# P05_BOOT_SET_KEY_LED_SPI_ADC.net
KiCad netlist of a schematic drawn in Altium Designer
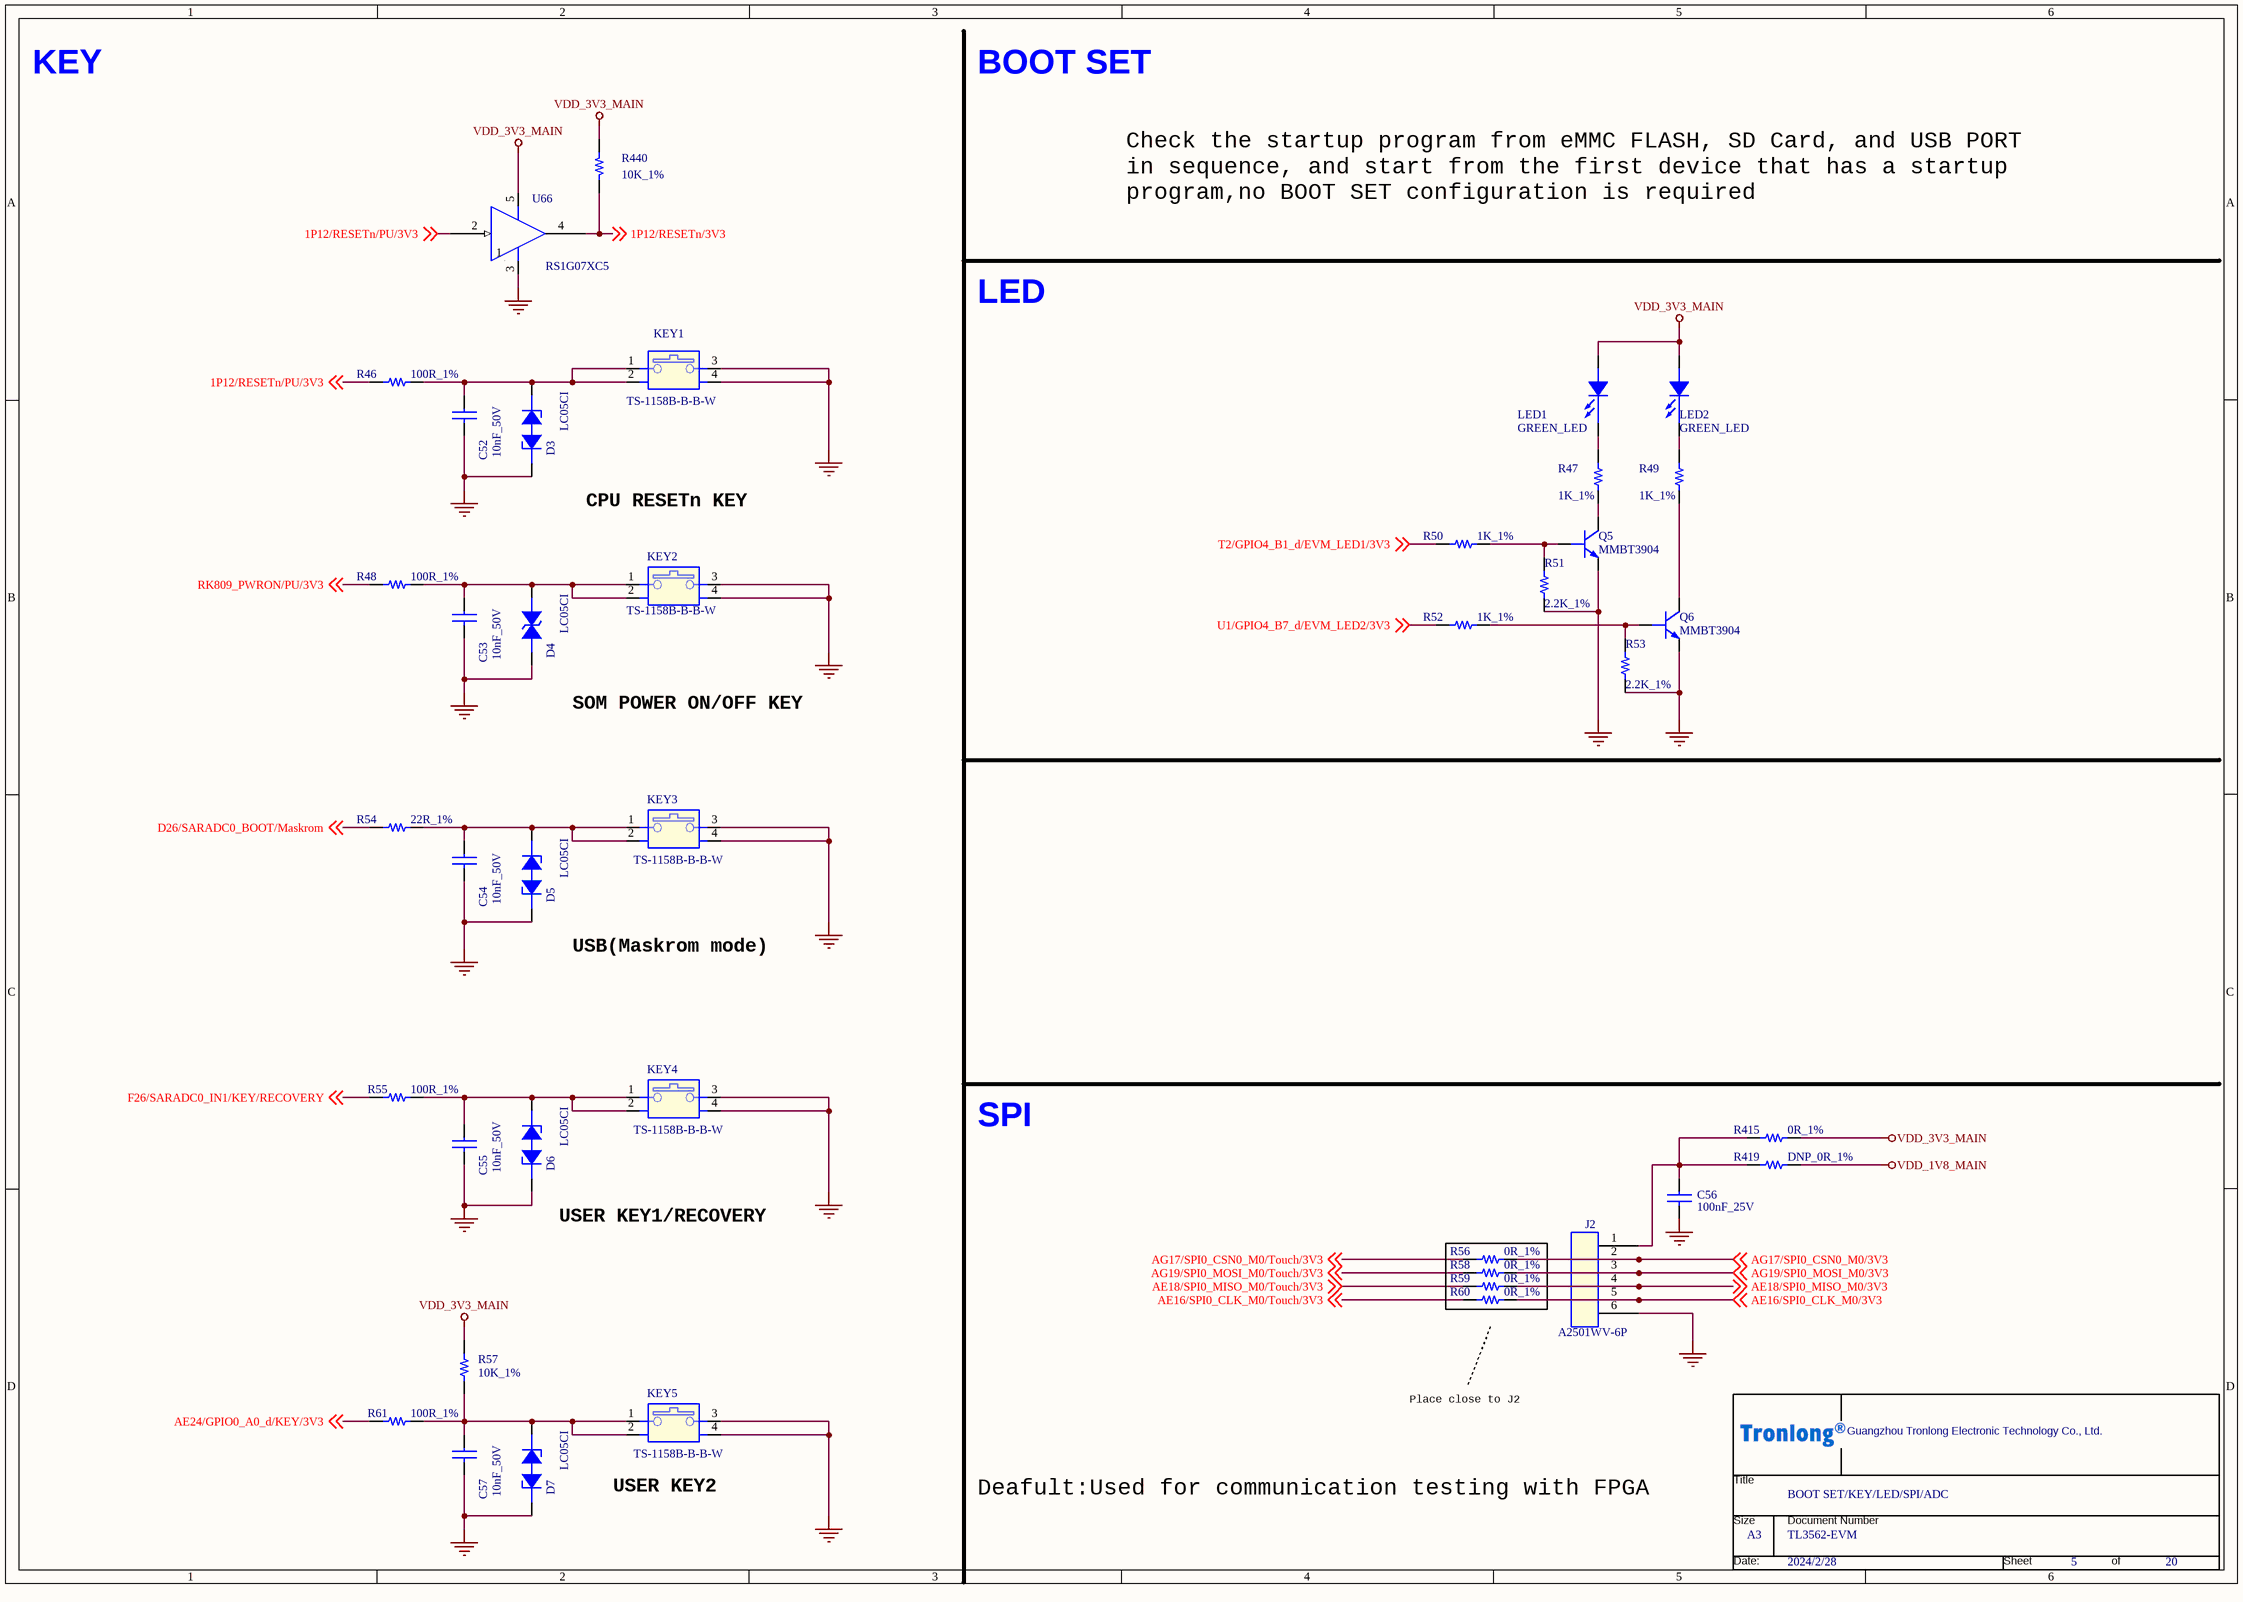
[diagram p0: P05_BOOT SET_KEY_LED_SPI_ADC.SchDoc]

(export (version "E")
  (design (tool "Eeschema 10.0.6"))
  (components
    (comp (ref "C52")
      (value "10nF_50V")
      (footprint "C0402")
      (description "贴片陶瓷电容,10nF,10%,50V,X7R")
      (libsource (lib "*") (part "CAP NP_Dup2"))
    )
    (comp (ref "C53")
      (value "10nF_50V")
      (footprint "C0402")
      (description "贴片陶瓷电容,10nF,10%,50V,X7R")
      (libsource (lib "*") (part "CAP NP_Dup2"))
    )
    (comp (ref "C54")
      (value "10nF_50V")
      (footprint "C0402")
      (description "贴片陶瓷电容,10nF,10%,50V,X7R")
      (libsource (lib "*") (part "CAP NP_Dup2"))
    )
    (comp (ref "C55")
      (value "10nF_50V")
      (footprint "C0402")
      (description "贴片陶瓷电容,10nF,10%,50V,X7R")
      (libsource (lib "*") (part "CAP NP_Dup2"))
    )
    (comp (ref "C56")
      (value "100nF_25V")
      (footprint "C0402")
      (description "贴片陶瓷电容,100nF,10%,25V,X5R")
      (libsource (lib "*") (part "CAP NP_Dup3"))
    )
    (comp (ref "C57")
      (value "10nF_50V")
      (footprint "C0402")
      (description "贴片陶瓷电容,10nF,10%,50V,X7R")
      (libsource (lib "*") (part "CAP NP_Dup2"))
    )
    (comp (ref "D3")
      (value "LC05CI")
      (footprint "SOD323_BI")
      (description "TVS二极管,VRWM=5V,VBR=6V,一组,双向,30KV,30KV")
      (fields
        (field (name "MANUFACTURER PART NUMBER") "PESD3V3L1BA")
        (field (name "MANUFACTURER") "上海雷卯电子科技有限公司（Leiditech）")
      )
      (libsource (lib "*") (part "DIODE BREAKDOWN_2"))
    )
    (comp (ref "D4")
      (value "LC05CI")
      (footprint "SOD323_BI")
      (description "TVS二极管,VRWM=5V,VBR=6V,一组,双向,30KV,30KV")
      (fields
        (field (name "MANUFACTURER PART NUMBER") "PESD3V3L1BA")
        (field (name "MANUFACTURER") "上海雷卯电子科技有限公司（Leiditech）")
      )
      (libsource (lib "*") (part "DIODE-BI"))
    )
    (comp (ref "D5")
      (value "LC05CI")
      (footprint "SOD323_BI")
      (description "TVS二极管,VRWM=5V,VBR=6V,一组,双向,30KV,30KV")
      (fields
        (field (name "MANUFACTURER") "上海雷卯电子科技有限公司（Leiditech）")
        (field (name "MANUFACTURER PART NUMBER") "PESD3V3L1BA")
      )
      (libsource (lib "*") (part "DIODE BREAKDOWN_2"))
    )
    (comp (ref "D6")
      (value "LC05CI")
      (footprint "SOD323_BI")
      (description "TVS二极管,VRWM=5V,VBR=6V,一组,双向,30KV,30KV")
      (fields
        (field (name "MANUFACTURER PART NUMBER") "PESD3V3L1BA")
        (field (name "MANUFACTURER") "上海雷卯电子科技有限公司（Leiditech）")
      )
      (libsource (lib "*") (part "DIODE BREAKDOWN_2"))
    )
    (comp (ref "D7")
      (value "LC05CI")
      (footprint "SOD323_BI")
      (description "TVS二极管,VRWM=5V,VBR=6V,一组,双向,30KV,30KV")
      (fields
        (field (name "MANUFACTURER") "上海雷卯电子科技有限公司（Leiditech）")
        (field (name "MANUFACTURER PART NUMBER") "PESD3V3L1BA")
      )
      (libsource (lib "*") (part "DIODE BREAKDOWN_2"))
    )
    (comp (ref "J2")
      (value "A2501WV-6P")
      (footprint "CON_XH_1x6P_2D54_H_M_DIP")
      (description "XH2.54  6P 连接器 180度")
      (fields (field (name "MANUFACTURER") "深圳市长江连接器有限公司（CJT）"))
      (libsource (lib "*") (part "CON6_Dup1"))
    )
    (comp (ref "KEY1")
      (value "TS-1158B-B-B-W")
      (footprint "TS-1158B-B-B-W")
      (description "四脚方形按键6.4x6.5，2.5mm+1.8mm，白色硅胶键帽")
      (fields (field (name "MANUFACTURER") "广东星坤科技股份有限公司（XKB）"))
      (libsource (lib "*") (part "SW PUSHBUTTON-SPST SHIELD_0"))
    )
    (comp (ref "KEY2")
      (value "TS-1158B-B-B-W")
      (footprint "TS-1158B-B-B-W")
      (description "四脚方形按键6.4x6.5，2.5mm+1.8mm，白色硅胶键帽")
      (fields (field (name "MANUFACTURER") "广东星坤科技股份有限公司（XKB）"))
      (libsource (lib "*") (part "SW PUSHBUTTON-SPST SHIELD_0"))
    )
    (comp (ref "KEY3")
      (value "TS-1158B-B-B-W")
      (footprint "TS-1158B-B-B-W")
      (description "四脚方形按键6.4x6.5，2.5mm+1.8mm，白色硅胶键帽")
      (fields (field (name "MANUFACTURER") "广东星坤科技股份有限公司（XKB）"))
      (libsource (lib "*") (part "SW PUSHBUTTON-SPST SHIELD_0"))
    )
    (comp (ref "KEY4")
      (value "TS-1158B-B-B-W")
      (footprint "TS-1158B-B-B-W")
      (description "四脚方形按键6.4x6.5，2.5mm+1.8mm，白色硅胶键帽")
      (fields (field (name "MANUFACTURER") "广东星坤科技股份有限公司（XKB）"))
      (libsource (lib "*") (part "SW PUSHBUTTON-SPST SHIELD_0"))
    )
    (comp (ref "KEY5")
      (value "TS-1158B-B-B-W")
      (footprint "TS-1158B-B-B-W")
      (description "四脚方形按键6.4x6.5，2.5mm+1.8mm，白色硅胶键帽")
      (fields (field (name "MANUFACTURER") "广东星坤科技股份有限公司（XKB）"))
      (libsource (lib "*") (part "SW PUSHBUTTON-SPST SHIELD_0"))
    )
    (comp (ref "LED1")
      (value "GREEN_LED")
      (footprint "CON_2P_3MM")
      (description "直插式发光二极管,绿色,带灯座")
      (fields
        (field (name "MANUFACTURER") "深圳市巨弘光电有限公司（JUHLIGHT）")
        (field (name "MANUFACTURER PARTNUMBER") "JH-03B2YG1E-DL")
      )
      (libsource (lib "*") (part "LED_0"))
    )
    (comp (ref "LED2")
      (value "GREEN_LED")
      (footprint "CON_2P_3MM")
      (description "直插式发光二极管,绿色,带灯座")
      (fields
        (field (name "MANUFACTURER PARTNUMBER") "JH-03B2YG1E-DL")
        (field (name "MANUFACTURER") "深圳市巨弘光电有限公司（JUHLIGHT）")
      )
      (libsource (lib "*") (part "LED_0"))
    )
    (comp (ref "Q5")
      (value "MMBT3904")
      (footprint "SOT23-3_DBZ3")
      (description "BJT,NPN,Vceo=40V,Ic=200mA,fT=300MHz,PD=200mW")
      (fields (field (name "MANUFACTURER") "江苏长晶科技有限公司（JSCJ）"))
      (libsource (lib "*") (part "MMBT3904/SOT"))
    )
    (comp (ref "Q6")
      (value "MMBT3904")
      (footprint "SOT23-3_DBZ3")
      (description "BJT,NPN,Vceo=40V,Ic=200mA,fT=300MHz,PD=200mW")
      (fields (field (name "MANUFACTURER") "江苏长晶科技有限公司（JSCJ）"))
      (libsource (lib "*") (part "MMBT3904/SOT"))
    )
    (comp (ref "R46")
      (value "100R_1%")
      (footprint "R0603")
      (description "贴片电阻,100R,±1%,1/10W")
      (libsource (lib "*") (part "Resistor_Dup2"))
    )
    (comp (ref "R47")
      (value "1K_1%")
      (footprint "R0402")
      (description "贴片电阻,1K,±1%,1/16W")
      (libsource (lib "*") (part "Resistor_Dup3"))
    )
    (comp (ref "R48")
      (value "100R_1%")
      (footprint "R0603")
      (description "贴片电阻,100R,±1%,1/10W")
      (libsource (lib "*") (part "Resistor_Dup2"))
    )
    (comp (ref "R49")
      (value "1K_1%")
      (footprint "R0402")
      (description "贴片电阻,1K,±1%,1/16W")
      (libsource (lib "*") (part "Resistor_Dup3"))
    )
    (comp (ref "R50")
      (value "1K_1%")
      (footprint "R0402")
      (description "贴片电阻,1K,±1%,1/16W")
      (libsource (lib "*") (part "Resistor_Dup3"))
    )
    (comp (ref "R51")
      (value "2.2K_1%")
      (footprint "R0603")
      (description "贴片电阻,2.2K,±1%,1/10W")
      (libsource (lib "*") (part "Resistor_Dup3"))
    )
    (comp (ref "R52")
      (value "1K_1%")
      (footprint "R0402")
      (description "贴片电阻,1K,±1%,1/16W")
      (libsource (lib "*") (part "Resistor_Dup3"))
    )
    (comp (ref "R53")
      (value "2.2K_1%")
      (footprint "R0603")
      (description "贴片电阻,2.2K,±1%,1/10W")
      (libsource (lib "*") (part "Resistor_Dup3"))
    )
    (comp (ref "R54")
      (value "22R_1%")
      (footprint "R0402")
      (description "贴片电阻,22R,±1%,1/16W")
      (libsource (lib "*") (part "Resistor_Dup2"))
    )
    (comp (ref "R55")
      (value "100R_1%")
      (footprint "R0603")
      (description "贴片电阻,100R,±1%,1/10W")
      (libsource (lib "*") (part "Resistor_Dup2"))
    )
    (comp (ref "R56")
      (value "0R_1%")
      (footprint "R0402")
      (description "0R,±1%,R0402,≥1/16W")
      (libsource (lib "*") (part "Resistor_Dup3"))
    )
    (comp (ref "R57")
      (value "10K_1%")
      (footprint "R0402")
      (description "贴片电阻,10K,±1%,1/16W")
      (libsource (lib "*") (part "Resistor_Dup2"))
    )
    (comp (ref "R58")
      (value "0R_1%")
      (footprint "R0402")
      (description "0R,±1%,R0402,≥1/16W")
      (libsource (lib "*") (part "Resistor_Dup3"))
    )
    (comp (ref "R59")
      (value "0R_1%")
      (footprint "R0402")
      (description "0R,±1%,R0402,≥1/16W")
      (libsource (lib "*") (part "Resistor_Dup3"))
    )
    (comp (ref "R60")
      (value "0R_1%")
      (footprint "R0402")
      (description "0R,±1%,R0402,≥1/16W")
      (libsource (lib "*") (part "Resistor_Dup3"))
    )
    (comp (ref "R61")
      (value "100R_1%")
      (footprint "R0603")
      (description "贴片电阻,100R,±1%,1/10W")
      (libsource (lib "*") (part "Resistor_Dup2"))
    )
    (comp (ref "R415")
      (value "0R_1%")
      (footprint "R0603")
      (description "0R,±1%,R0603,≥1/10W")
      (libsource (lib "*") (part "Resistor_Dup3"))
    )
    (comp (ref "R419")
      (value "DNP_0R_1%")
      (footprint "R0603")
      (description "贴片电阻,0R,±1%,1/10W")
      (libsource (lib "*") (part "Resistor_Dup3"))
    )
    (comp (ref "R440")
      (value "10K_1%")
      (footprint "R0402")
      (description "贴片电阻,10K,±1%,1/16W")
      (libsource (lib "*") (part "Resistor"))
    )
    (comp (ref "U66")
      (value "RS1G07XC5")
      (footprint "SC70-5-43M")
      (description "1个1位缓冲器")
      (fields (field (name "MFR") "TI") (field (name "TIINTPARTNUMBER") "1A0269"))
      (libsource (lib "*") (part "1A_SN74LVC1G07"))
    )
  )
  (nets
    (net (code "1") (name "1P12{slash}RESETn{slash}3V3") (class "Default")
      (node (ref "R440") (pin "1") (pinfunction "1_1") (pintype "passive"))
      (node (ref "U66") (pin "4") (pinfunction "Y_4") (pintype "open_collector"))
    )
    (net (code "2") (name "1P12{slash}RESETn{slash}PU{slash}3V3") (class "Default")
      (node (ref "R46") (pin "1") (pinfunction "1_1") (pintype "passive"))
      (node (ref "U66") (pin "2") (pinfunction "A_2") (pintype "input"))
    )
    (net (code "3") (name "AE16{slash}SPI0_CLK_M0{slash}3V3") (class "Default")
      (node (ref "J2") (pin "5") (pinfunction "5_5") (pintype "passive"))
      (node (ref "R60") (pin "2") (pinfunction "2_2") (pintype "passive"))
    )
    (net (code "4") (name "AE16{slash}SPI0_CLK_M0{slash}Touch{slash}3V3") (class "Default")
      (node (ref "R60") (pin "1") (pinfunction "1_1") (pintype "passive"))
    )
    (net (code "5") (name "AE18{slash}SPI0_MISO_M0{slash}3V3") (class "Default")
      (node (ref "J2") (pin "4") (pinfunction "4_4") (pintype "passive"))
      (node (ref "R59") (pin "2") (pinfunction "2_2") (pintype "passive"))
    )
    (net (code "6") (name "AE18{slash}SPI0_MISO_M0{slash}Touch{slash}3V3") (class "Default")
      (node (ref "R59") (pin "1") (pinfunction "1_1") (pintype "passive"))
    )
    (net (code "7") (name "AE24{slash}GPIO0_A0_d{slash}KEY{slash}3V3") (class "Default")
      (node (ref "R61") (pin "1") (pinfunction "1_1") (pintype "passive"))
    )
    (net (code "8") (name "AG17{slash}SPI0_CSN0_M0{slash}3V3") (class "Default")
      (node (ref "J2") (pin "2") (pinfunction "2_2") (pintype "passive"))
      (node (ref "R56") (pin "2") (pinfunction "2_2") (pintype "passive"))
    )
    (net (code "9") (name "AG17{slash}SPI0_CSN0_M0{slash}Touch{slash}3V3") (class "Default")
      (node (ref "R56") (pin "1") (pinfunction "1_1") (pintype "passive"))
    )
    (net (code "10") (name "AG19{slash}SPI0_MOSI_M0{slash}3V3") (class "Default")
      (node (ref "J2") (pin "3") (pinfunction "3_3") (pintype "passive"))
      (node (ref "R58") (pin "2") (pinfunction "2_2") (pintype "passive"))
    )
    (net (code "11") (name "AG19{slash}SPI0_MOSI_M0{slash}Touch{slash}3V3") (class "Default")
      (node (ref "R58") (pin "1") (pinfunction "1_1") (pintype "passive"))
    )
    (net (code "12") (name "D26{slash}SARADC0_BOOT{slash}Maskrom") (class "Default")
      (node (ref "R54") (pin "1") (pinfunction "1_1") (pintype "passive"))
    )
    (net (code "13") (name "F26{slash}SARADC0_IN1{slash}KEY{slash}RECOVERY") (class "Default")
      (node (ref "R55") (pin "1") (pinfunction "1_1") (pintype "passive"))
    )
    (net (code "14") (name "GND") (class "Default")
      (node (ref "C52") (pin "2") (pinfunction "2_2") (pintype "passive"))
      (node (ref "C53") (pin "2") (pinfunction "2_2") (pintype "passive"))
      (node (ref "C54") (pin "2") (pinfunction "2_2") (pintype "passive"))
      (node (ref "C55") (pin "2") (pinfunction "2_2") (pintype "passive"))
      (node (ref "C56") (pin "2") (pinfunction "2_2") (pintype "passive"))
      (node (ref "C57") (pin "2") (pinfunction "2_2") (pintype "passive"))
      (node (ref "D3") (pin "2") (pinfunction "CATHODE2_2") (pintype "passive"))
      (node (ref "D4") (pin "2") (pinfunction "2_2") (pintype "passive"))
      (node (ref "D5") (pin "2") (pinfunction "CATHODE2_2") (pintype "passive"))
      (node (ref "D6") (pin "2") (pinfunction "CATHODE2_2") (pintype "passive"))
      (node (ref "D7") (pin "2") (pinfunction "CATHODE2_2") (pintype "passive"))
      (node (ref "J2") (pin "6") (pinfunction "6_6") (pintype "passive"))
      (node (ref "KEY1") (pin "3") (pinfunction "3_3") (pintype "passive"))
      (node (ref "KEY1") (pin "4") (pinfunction "4_4") (pintype "passive"))
      (node (ref "KEY2") (pin "3") (pinfunction "3_3") (pintype "passive"))
      (node (ref "KEY2") (pin "4") (pinfunction "4_4") (pintype "passive"))
      (node (ref "KEY3") (pin "3") (pinfunction "3_3") (pintype "passive"))
      (node (ref "KEY3") (pin "4") (pinfunction "4_4") (pintype "passive"))
      (node (ref "KEY4") (pin "3") (pinfunction "3_3") (pintype "passive"))
      (node (ref "KEY4") (pin "4") (pinfunction "4_4") (pintype "passive"))
      (node (ref "KEY5") (pin "3") (pinfunction "3_3") (pintype "passive"))
      (node (ref "KEY5") (pin "4") (pinfunction "4_4") (pintype "passive"))
      (node (ref "Q5") (pin "2") (pinfunction "E_2") (pintype "passive"))
      (node (ref "Q6") (pin "2") (pinfunction "E_2") (pintype "passive"))
      (node (ref "R51") (pin "1") (pinfunction "1_1") (pintype "passive"))
      (node (ref "R53") (pin "1") (pinfunction "1_1") (pintype "passive"))
      (node (ref "U66") (pin "3") (pinfunction "GND_3") (pintype "power_in"))
    )
    (net (code "15") (name "Net-(C53-Pad1)") (class "Default")
      (node (ref "C53") (pin "1") (pinfunction "1_1") (pintype "passive"))
      (node (ref "D4") (pin "1") (pinfunction "1_1") (pintype "passive"))
      (node (ref "KEY2") (pin "1") (pinfunction "1_1") (pintype "passive"))
      (node (ref "KEY2") (pin "2") (pinfunction "2_2") (pintype "passive"))
      (node (ref "R48") (pin "2") (pinfunction "2_2") (pintype "passive"))
    )
    (net (code "16") (name "Net-(C56-Pad1)") (class "Default")
      (node (ref "C56") (pin "1") (pinfunction "1_1") (pintype "passive"))
      (node (ref "J2") (pin "1") (pinfunction "1_1") (pintype "passive"))
      (node (ref "R415") (pin "1") (pinfunction "1_1") (pintype "passive"))
      (node (ref "R419") (pin "1") (pinfunction "1_1") (pintype "passive"))
    )
    (net (code "17") (name "Net-(D3-ANODE1)") (class "Default")
      (node (ref "C52") (pin "1") (pinfunction "1_1") (pintype "passive"))
      (node (ref "D3") (pin "1") (pinfunction "ANODE1_1") (pintype "passive"))
      (node (ref "KEY1") (pin "1") (pinfunction "1_1") (pintype "passive"))
      (node (ref "KEY1") (pin "2") (pinfunction "2_2") (pintype "passive"))
      (node (ref "R46") (pin "2") (pinfunction "2_2") (pintype "passive"))
    )
    (net (code "18") (name "Net-(D5-ANODE1)") (class "Default")
      (node (ref "C54") (pin "1") (pinfunction "1_1") (pintype "passive"))
      (node (ref "D5") (pin "1") (pinfunction "ANODE1_1") (pintype "passive"))
      (node (ref "KEY3") (pin "1") (pinfunction "1_1") (pintype "passive"))
      (node (ref "KEY3") (pin "2") (pinfunction "2_2") (pintype "passive"))
      (node (ref "R54") (pin "2") (pinfunction "2_2") (pintype "passive"))
    )
    (net (code "19") (name "Net-(D6-ANODE1)") (class "Default")
      (node (ref "C55") (pin "1") (pinfunction "1_1") (pintype "passive"))
      (node (ref "D6") (pin "1") (pinfunction "ANODE1_1") (pintype "passive"))
      (node (ref "KEY4") (pin "1") (pinfunction "1_1") (pintype "passive"))
      (node (ref "KEY4") (pin "2") (pinfunction "2_2") (pintype "passive"))
      (node (ref "R55") (pin "2") (pinfunction "2_2") (pintype "passive"))
    )
    (net (code "20") (name "Net-(D7-ANODE1)") (class "Default")
      (node (ref "C57") (pin "1") (pinfunction "1_1") (pintype "passive"))
      (node (ref "D7") (pin "1") (pinfunction "ANODE1_1") (pintype "passive"))
      (node (ref "KEY5") (pin "1") (pinfunction "1_1") (pintype "passive"))
      (node (ref "KEY5") (pin "2") (pinfunction "2_2") (pintype "passive"))
      (node (ref "R57") (pin "1") (pinfunction "1_1") (pintype "passive"))
      (node (ref "R61") (pin "2") (pinfunction "2_2") (pintype "passive"))
    )
    (net (code "21") (name "Net-(LED1-ANODE)") (class "Default")
      (node (ref "LED1") (pin "2") (pinfunction "ANODE_2") (pintype "passive"))
      (node (ref "R47") (pin "2") (pinfunction "2_2") (pintype "passive"))
    )
    (net (code "22") (name "Net-(LED2-ANODE)") (class "Default")
      (node (ref "LED2") (pin "2") (pinfunction "ANODE_2") (pintype "passive"))
      (node (ref "R49") (pin "2") (pinfunction "2_2") (pintype "passive"))
    )
    (net (code "23") (name "Net-(Q5-B)") (class "Default")
      (node (ref "Q5") (pin "1") (pinfunction "B_1") (pintype "passive"))
      (node (ref "R50") (pin "1") (pinfunction "1_1") (pintype "passive"))
      (node (ref "R51") (pin "2") (pinfunction "2_2") (pintype "passive"))
    )
    (net (code "24") (name "Net-(Q5-C)") (class "Default")
      (node (ref "Q5") (pin "3") (pinfunction "C_3") (pintype "passive"))
      (node (ref "R47") (pin "1") (pinfunction "1_1") (pintype "passive"))
    )
    (net (code "25") (name "Net-(Q6-B)") (class "Default")
      (node (ref "Q6") (pin "1") (pinfunction "B_1") (pintype "passive"))
      (node (ref "R52") (pin "1") (pinfunction "1_1") (pintype "passive"))
      (node (ref "R53") (pin "2") (pinfunction "2_2") (pintype "passive"))
    )
    (net (code "26") (name "Net-(Q6-C)") (class "Default")
      (node (ref "Q6") (pin "3") (pinfunction "C_3") (pintype "passive"))
      (node (ref "R49") (pin "1") (pinfunction "1_1") (pintype "passive"))
    )
    (net (code "27") (name "RK809_PWRON{slash}PU{slash}3V3") (class "Default")
      (node (ref "R48") (pin "1") (pinfunction "1_1") (pintype "passive"))
    )
    (net (code "28") (name "T2{slash}GPIO4_B1_d{slash}EVM_LED1{slash}3V3") (class "Default")
      (node (ref "R50") (pin "2") (pinfunction "2_2") (pintype "passive"))
    )
    (net (code "29") (name "U1{slash}GPIO4_B7_d{slash}EVM_LED2{slash}3V3") (class "Default")
      (node (ref "R52") (pin "2") (pinfunction "2_2") (pintype "passive"))
    )
    (net (code "30") (name "VDD_1V8_MAIN") (class "Default")
      (node (ref "R419") (pin "2") (pinfunction "2_2") (pintype "passive"))
    )
    (net (code "31") (name "VDD_3V3_MAIN") (class "Default")
      (node (ref "LED1") (pin "1") (pinfunction "CATHODE_1") (pintype "passive"))
      (node (ref "LED2") (pin "1") (pinfunction "CATHODE_1") (pintype "passive"))
      (node (ref "R415") (pin "2") (pinfunction "2_2") (pintype "passive"))
      (node (ref "R440") (pin "2") (pinfunction "2_2") (pintype "passive"))
      (node (ref "R57") (pin "2") (pinfunction "2_2") (pintype "passive"))
      (node (ref "U66") (pin "5") (pinfunction "VCC_5") (pintype "power_in"))
    )
    (net (code "32") (name "unconnected-(U66-NC-Pad1)") (class "Default")
      (node (ref "U66") (pin "1") (pinfunction "NC_1") (pintype "passive"))
    )
  )
)
